# uart.net
KiCad netlist of a schematic drawn in EAGLE
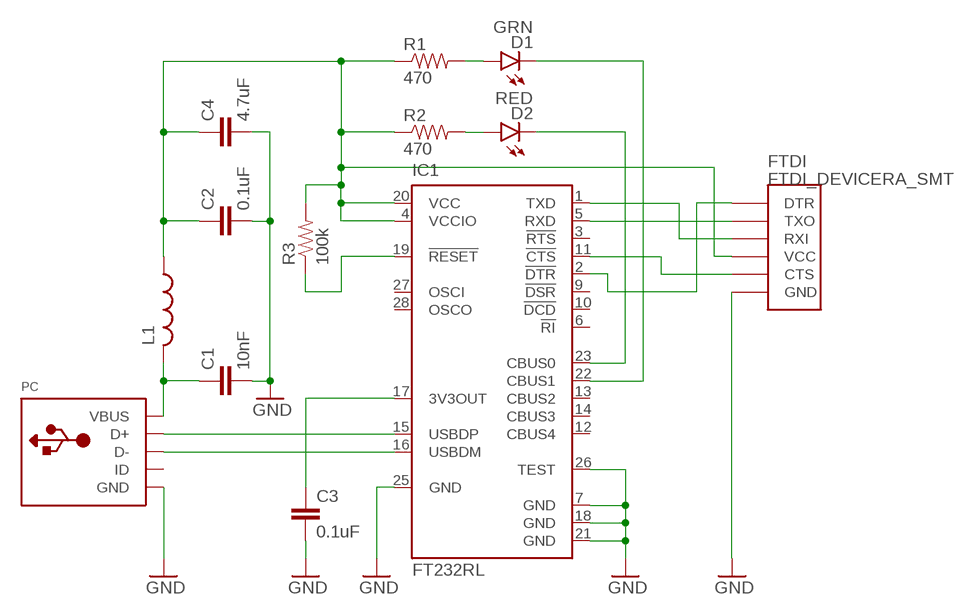
[diagram p0: schematic, sheet 1]

(export (version "E")
  (design (tool "Eeschema 10.0.6"))
  (components
    (comp (ref "C1")
      (value "10nF")
      (footprint "eagle-import:0603-CAP")
      (fields (field (name "MPN") "C0603C103J1RACTU"))
      (libsource (lib "eagle-import") (part "10NF/10000PF-50V-10%(0603)"))
    )
    (comp (ref "C2")
      (value "0.1uF")
      (footprint "eagle-import:0603-CAP")
      (fields (field (name "MPN") "C0603C104K4RAC7081"))
      (libsource (lib "eagle-import") (part "0.1UF-25V-5%(0603)"))
    )
    (comp (ref "C3")
      (value "0.1uF")
      (footprint "eagle-import:0603-CAP")
      (fields (field (name "MPN") "C0603C104K4RAC7081"))
      (libsource (lib "eagle-import") (part "0.1UF-25V-5%(0603)"))
    )
    (comp (ref "C4")
      (value "4.7uF")
      (footprint "eagle-import:0603-CAP")
      (fields (field (name "MPN") "0603F475Z100CT"))
      (libsource (lib "eagle-import") (part "4.7UF-6.3V-10%(0603)0603"))
    )
    (comp (ref "D1")
      (value "GRN")
      (footprint "eagle-import:LED-0603")
      (fields (field (name "MPN") "HSME-C191"))
      (libsource (lib "eagle-import") (part "LED-GREEN0603"))
    )
    (comp (ref "D2")
      (value "RED")
      (footprint "eagle-import:LED-0603")
      (fields (field (name "MPN") "HSMC-C120"))
      (libsource (lib "eagle-import") (part "LED-RED0603"))
    )
    (comp (ref "FTDI")
      (value "FTDI_DEVICERA_SMT")
      (footprint "eagle-import:FTDI_DEVICE_RA_SMT")
      (libsource (lib "eagle-import") (part "FTDI_DEVICERA_SMT"))
    )
    (comp (ref "IC1")
      (value "FT232RL")
      (footprint "eagle-import:SSOP28")
      (fields (field (name "MPN") "FT232RL-REEL"))
      (libsource (lib "eagle-import") (part "FT232RL"))
    )
    (comp (ref "L1")
      (value "L-USL2012C")
      (footprint "eagle-import:L2012C")
      (fields (field (name "MPN") "744052180"))
      (libsource (lib "eagle-import") (part "L-USL2012C"))
    )
    (comp (ref "PC")
      (value "USBMINIB")
      (footprint "eagle-import:USB-MINIB")
      (fields (field (name "MPN") "MUSB-B5-S-RA-TSMT-CS1"))
      (libsource (lib "eagle-import") (part "USBMINIB"))
    )
    (comp (ref "R1")
      (value "470")
      (footprint "eagle-import:0603-RES")
      (fields (field (name "MPN") "ERJ-P03F4700V"))
      (libsource (lib "eagle-import") (part "470OHM1/10W1%(0603)"))
    )
    (comp (ref "R2")
      (value "470")
      (footprint "eagle-import:0603-RES")
      (fields (field (name "MPN") "ERJ-P03F4700V"))
      (libsource (lib "eagle-import") (part "470OHM1/10W1%(0603)"))
    )
    (comp (ref "R3")
      (value "100k")
      (footprint "eagle-import:0603-RES")
      (fields (field (name "MPN") "ERA-3AEB104V"))
      (libsource (lib "eagle-import") (part "100KOHM-1/10W-1%(0603)"))
    )
  )
  (nets
    (net (code "1") (name "GND") (class "Default")
      (node (ref "C1") (pin "2") (pinfunction "2_2") (pintype "passive"))
      (node (ref "C2") (pin "2") (pinfunction "2_2") (pintype "passive"))
      (node (ref "C3") (pin "2") (pinfunction "2_2") (pintype "passive"))
      (node (ref "C4") (pin "2") (pinfunction "2_2") (pintype "passive"))
      (node (ref "FTDI") (pin "6") (pinfunction "GND_6") (pintype "bidirectional"))
      (node (ref "IC1") (pin "18") (pinfunction "GND_18") (pintype "power_in"))
      (node (ref "IC1") (pin "21") (pinfunction "GND_21") (pintype "power_in"))
      (node (ref "IC1") (pin "25") (pinfunction "GND_25") (pintype "power_in"))
      (node (ref "IC1") (pin "26") (pinfunction "TEST_26") (pintype "input"))
      (node (ref "IC1") (pin "7") (pinfunction "GND_7") (pintype "power_in"))
      (node (ref "PC") (pin "GND") (pinfunction "GND_GND") (pintype "power_in"))
    )
    (net (code "2") (name "Net-(C1-Pad1)") (class "Default")
      (node (ref "C1") (pin "1") (pinfunction "1_1") (pintype "passive"))
      (node (ref "L1") (pin "2") (pinfunction "2_2") (pintype "passive"))
      (node (ref "PC") (pin "VBUS") (pinfunction "VBUS_VBUS") (pintype "power_in"))
    )
    (net (code "3") (name "Net-(D1-PadA)") (class "Default")
      (node (ref "D1") (pin "A") (pinfunction "A_A") (pintype "passive"))
      (node (ref "R1") (pin "2") (pinfunction "2_2") (pintype "passive"))
    )
    (net (code "4") (name "Net-(D2-PadA)") (class "Default")
      (node (ref "D2") (pin "A") (pinfunction "A_A") (pintype "passive"))
      (node (ref "R2") (pin "2") (pinfunction "2_2") (pintype "passive"))
    )
    (net (code "5") (name "Net-(FTDI-CTS)") (class "Default")
      (node (ref "FTDI") (pin "5") (pinfunction "CTS_5") (pintype "bidirectional"))
      (node (ref "IC1") (pin "11") (pinfunction "~{CTS}_11") (pintype "input"))
    )
    (net (code "6") (name "Net-(FTDI-DTR)") (class "Default")
      (node (ref "FTDI") (pin "1") (pinfunction "DTR_1") (pintype "bidirectional"))
      (node (ref "IC1") (pin "2") (pinfunction "~{DTR}_2") (pintype "output"))
    )
    (net (code "7") (name "Net-(FTDI-RXI)") (class "Default")
      (node (ref "FTDI") (pin "3") (pinfunction "RXI_3") (pintype "bidirectional"))
      (node (ref "IC1") (pin "1") (pinfunction "TXD_1") (pintype "output"))
    )
    (net (code "8") (name "Net-(FTDI-TXO)") (class "Default")
      (node (ref "FTDI") (pin "2") (pinfunction "TXO_2") (pintype "bidirectional"))
      (node (ref "IC1") (pin "5") (pinfunction "RXD_5") (pintype "input"))
    )
    (net (code "9") (name "Net-(FTDI-VCC)") (class "Default")
      (node (ref "C2") (pin "1") (pinfunction "1_1") (pintype "passive"))
      (node (ref "C4") (pin "1") (pinfunction "1_1") (pintype "passive"))
      (node (ref "FTDI") (pin "4") (pinfunction "VCC_4") (pintype "bidirectional"))
      (node (ref "IC1") (pin "20") (pinfunction "VCC_20") (pintype "power_in"))
      (node (ref "IC1") (pin "4") (pinfunction "VCCIO_4") (pintype "power_in"))
      (node (ref "L1") (pin "1") (pinfunction "1_1") (pintype "passive"))
      (node (ref "R1") (pin "1") (pinfunction "1_1") (pintype "passive"))
      (node (ref "R2") (pin "1") (pinfunction "1_1") (pintype "passive"))
      (node (ref "R3") (pin "2") (pinfunction "2_2") (pintype "passive"))
    )
    (net (code "10") (name "Net-(IC1-3V3OUT)") (class "Default")
      (node (ref "C3") (pin "1") (pinfunction "1_1") (pintype "passive"))
      (node (ref "IC1") (pin "17") (pinfunction "3V3OUT_17") (pintype "output"))
    )
    (net (code "11") (name "Net-(IC1-CBUS0)") (class "Default")
      (node (ref "D2") (pin "C") (pinfunction "C_C") (pintype "passive"))
      (node (ref "IC1") (pin "23") (pinfunction "CBUS0_23") (pintype "bidirectional"))
    )
    (net (code "12") (name "Net-(IC1-CBUS1)") (class "Default")
      (node (ref "D1") (pin "C") (pinfunction "C_C") (pintype "passive"))
      (node (ref "IC1") (pin "22") (pinfunction "CBUS1_22") (pintype "bidirectional"))
    )
    (net (code "13") (name "Net-(IC1-USBDM)") (class "Default")
      (node (ref "IC1") (pin "16") (pinfunction "USBDM_16") (pintype "bidirectional"))
      (node (ref "PC") (pin "D-") (pinfunction "D-_D-") (pintype "bidirectional"))
    )
    (net (code "14") (name "Net-(IC1-USBDP)") (class "Default")
      (node (ref "IC1") (pin "15") (pinfunction "USBDP_15") (pintype "bidirectional"))
      (node (ref "PC") (pin "D+") (pinfunction "D+_D+") (pintype "bidirectional"))
    )
    (net (code "15") (name "Net-(IC1-~{RESET})") (class "Default")
      (node (ref "IC1") (pin "19") (pinfunction "~{RESET}_19") (pintype "input"))
      (node (ref "R3") (pin "1") (pinfunction "1_1") (pintype "passive"))
    )
    (net (code "16") (name "unconnected-(IC1-CBUS2-Pad13)") (class "Default")
      (node (ref "IC1") (pin "13") (pinfunction "CBUS2_13") (pintype "bidirectional"))
    )
    (net (code "17") (name "unconnected-(IC1-CBUS3-Pad14)") (class "Default")
      (node (ref "IC1") (pin "14") (pinfunction "CBUS3_14") (pintype "bidirectional"))
    )
    (net (code "18") (name "unconnected-(IC1-CBUS4-Pad12)") (class "Default")
      (node (ref "IC1") (pin "12") (pinfunction "CBUS4_12") (pintype "bidirectional"))
    )
    (net (code "19") (name "unconnected-(IC1-OSCI-Pad27)") (class "Default")
      (node (ref "IC1") (pin "27") (pinfunction "OSCI_27") (pintype "input"))
    )
    (net (code "20") (name "unconnected-(IC1-OSCO-Pad28)") (class "Default")
      (node (ref "IC1") (pin "28") (pinfunction "OSCO_28") (pintype "output"))
    )
    (net (code "21") (name "unconnected-(IC1-~{DCD}-Pad10)") (class "Default")
      (node (ref "IC1") (pin "10") (pinfunction "~{DCD}_10") (pintype "input"))
    )
    (net (code "22") (name "unconnected-(IC1-~{DSR}-Pad9)") (class "Default")
      (node (ref "IC1") (pin "9") (pinfunction "~{DSR}_9") (pintype "input"))
    )
    (net (code "23") (name "unconnected-(IC1-~{RI}-Pad6)") (class "Default")
      (node (ref "IC1") (pin "6") (pinfunction "~{RI}_6") (pintype "input"))
    )
    (net (code "24") (name "unconnected-(IC1-~{RTS}-Pad3)") (class "Default")
      (node (ref "IC1") (pin "3") (pinfunction "~{RTS}_3") (pintype "output"))
    )
    (net (code "25") (name "unconnected-(PC-PadID)") (class "Default")
      (node (ref "PC") (pin "ID") (pinfunction "ID_ID") (pintype "bidirectional"))
    )
  )
)
